# Buck-Boost_5-12V.net
KiCad netlist of a schematic drawn in Altium Designer
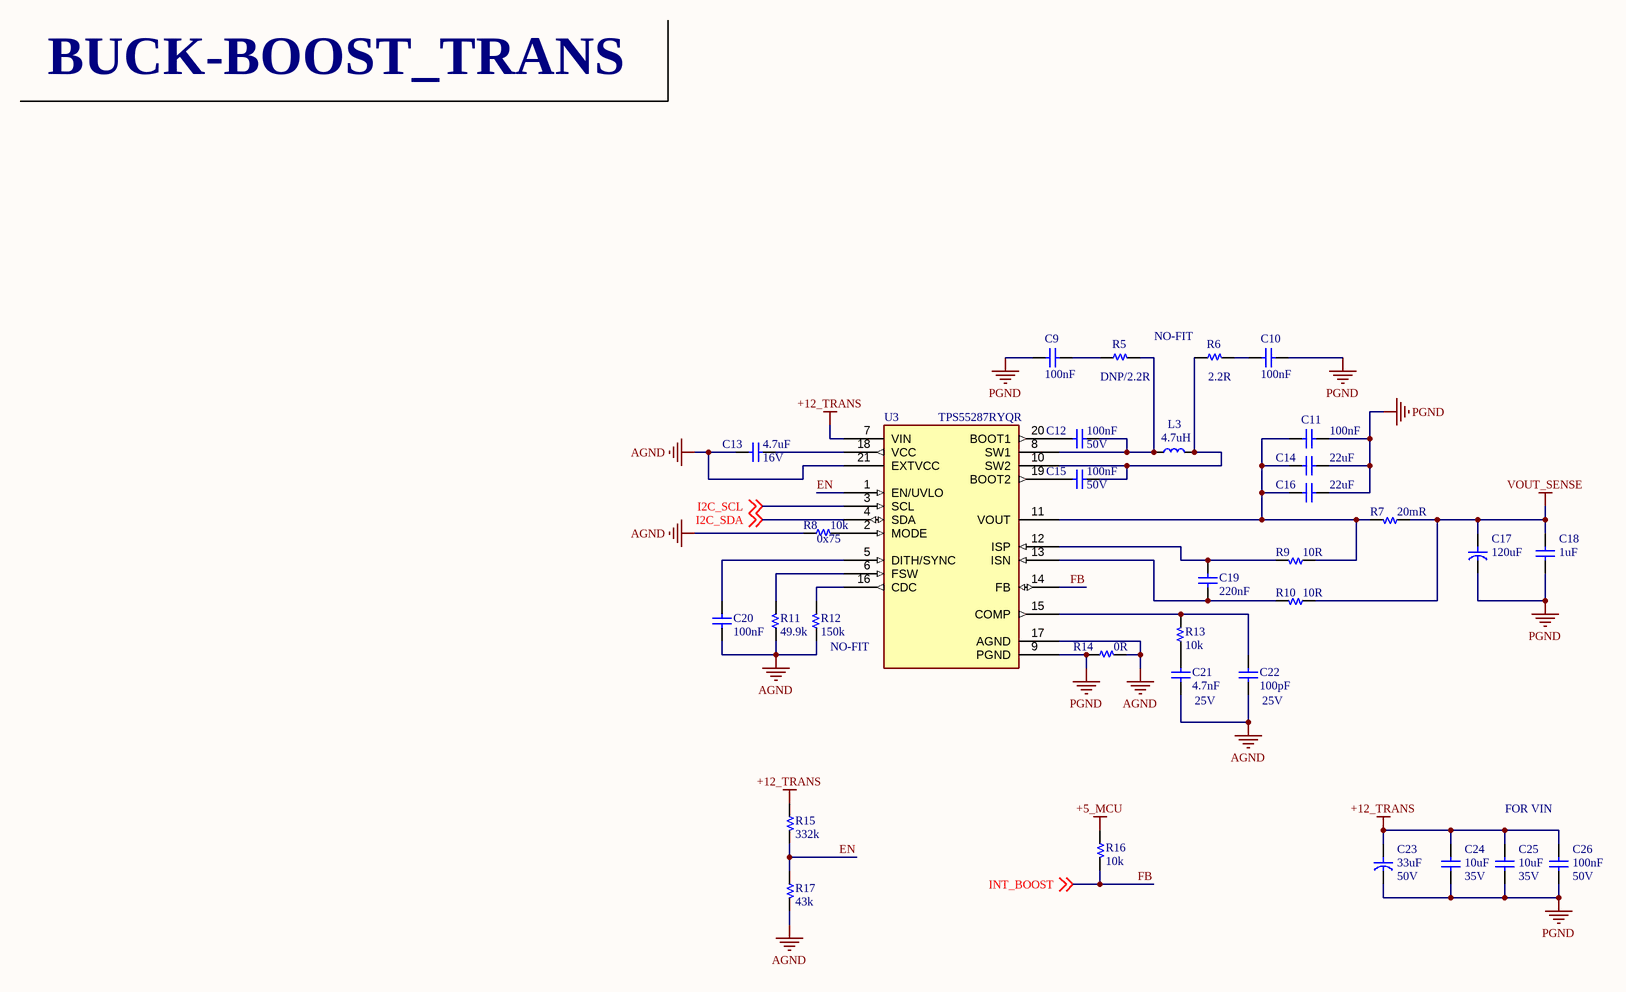
[diagram p0: Buck-Boost 5-12V.SchDoc]

(export (version "E")
  (design (tool "Eeschema 10.0.6"))
  (components
    (comp (ref "C9")
      (value "100nF")
      (footprint "C 0805")
      (description "CAP CER 0.1UF 50V X7R 0603")
      (libsource (lib "KIENASIY123_LIB") (part "Capacitor NP"))
    )
    (comp (ref "C10")
      (value "100nF")
      (footprint "C 0805")
      (description "Capacitor non-pol")
      (libsource (lib "KIENASIY123_LIB") (part "Capacitor NP"))
    )
    (comp (ref "C11")
      (value "100nF")
      (footprint "C 0402")
      (description "CAP CER 0.1UF 50V X7R 0603")
      (libsource (lib "KIENASIY123_LIB") (part "Capacitor NP"))
    )
    (comp (ref "C12")
      (value "100nF")
      (footprint "C 0603")
      (description "CAP CER 0.1UF 50V X7R 0603")
      (libsource (lib "KIENASIY123_LIB") (part "Capacitor NP"))
    )
    (comp (ref "C13")
      (value "4.7uF")
      (footprint "C 0402")
      (description "CAP CER 4.7UF 25V X6S 0603")
      (libsource (lib "KIENASIY123_LIB") (part "Capacitor NP"))
    )
    (comp (ref "C14")
      (value "22uF")
      (footprint "C 0603")
      (description "CAP CER 22UF 35V X5R 1206")
      (libsource (lib "KIENASIY123_LIB") (part "Capacitor NP"))
    )
    (comp (ref "C15")
      (value "100nF")
      (footprint "C 0603")
      (description "CAP CER 0.1UF 50V X7R 0603")
      (libsource (lib "KIENASIY123_LIB") (part "Capacitor NP"))
    )
    (comp (ref "C16")
      (value "22uF")
      (footprint "C 0603")
      (description "CAP CER 22UF 35V X5R 1206")
      (libsource (lib "KIENASIY123_LIB") (part "Capacitor NP"))
    )
    (comp (ref "C17")
      (value "120uF")
      (footprint "C SMD TAN 2917 (E)")
      (description "T543X107M025AHE060")
      (libsource (lib "KIENASIY123_LIB") (part "Capacitor"))
    )
    (comp (ref "C18")
      (value "1uF")
      (footprint "C 0603")
      (description "CAP CER 22UF 35V X5R 1206")
      (libsource (lib "KIENASIY123_LIB") (part "Capacitor NP"))
    )
    (comp (ref "C19")
      (value "220nF")
      (footprint "C 0402")
      (description "Capacitor non-pol")
      (libsource (lib "KIENASIY123_LIB") (part "Capacitor NP"))
    )
    (comp (ref "C20")
      (value "100nF")
      (footprint "C 0402")
      (description "CAP CER 0.1UF 50V X7R 0603")
      (libsource (lib "KIENASIY123_LIB") (part "Capacitor NP"))
    )
    (comp (ref "C21")
      (value "4.7nF")
      (footprint "C 0402")
      (description "Capacitor non-pol")
      (libsource (lib "KIENASIY123_LIB") (part "Capacitor NP"))
    )
    (comp (ref "C22")
      (value "100pF")
      (footprint "C 0402")
      (description "Capacitor non-pol")
      (libsource (lib "KIENASIY123_LIB") (part "Capacitor NP"))
    )
    (comp (ref "C23")
      (value "33uF")
      (footprint "C SMD TAN 2917 (E)")
      (description "T543X336M050AHE0407505")
      (libsource (lib "KIENASIY123_LIB") (part "Capacitor"))
    )
    (comp (ref "C24")
      (value "10uF")
      (footprint "C 0603")
      (description "CAP CER 10UF 35V X5R 0603")
      (libsource (lib "KIENASIY123_LIB") (part "Capacitor NP"))
    )
    (comp (ref "C25")
      (value "10uF")
      (footprint "C 0603")
      (description "CAP CER 10UF 35V X5R 0603")
      (libsource (lib "KIENASIY123_LIB") (part "Capacitor NP"))
    )
    (comp (ref "C26")
      (value "100nF")
      (footprint "C 0402")
      (description "CAP CER 0.1UF 50V X7R 0603")
      (libsource (lib "KIENASIY123_LIB") (part "Capacitor NP"))
    )
    (comp (ref "L3")
      (value "4.7uH")
      (footprint "Inductor SMD 6x5.7x4.8")
      (description "EXLA1V0505-4R7-R")
      (libsource (lib "KIENASIY123_LIB") (part "Inductor"))
    )
    (comp (ref "R5")
      (value "DNP/2.2R")
      (footprint "R 1206")
      (description "Resistor")
      (libsource (lib "KIENASIY123_LIB") (part "Resistor"))
    )
    (comp (ref "R6")
      (value "2.2R")
      (footprint "R 1206")
      (description "Resistor")
      (libsource (lib "KIENASIY123_LIB") (part "Resistor"))
    )
    (comp (ref "R7")
      (value "20mR")
      (footprint "R 1206")
      (description "Resistor")
      (libsource (lib "KIENASIY123_LIB") (part "Resistor"))
    )
    (comp (ref "R8")
      (value "10k")
      (footprint "R 0402")
      (description "RES 10K OHM 1% 1/10W 0603")
      (libsource (lib "KIENASIY123_LIB") (part "Resistor"))
    )
    (comp (ref "R9")
      (value "10R")
      (footprint "R 0402")
      (description "Resistor")
      (libsource (lib "KIENASIY123_LIB") (part "Resistor"))
    )
    (comp (ref "R10")
      (value "10R")
      (footprint "R 0402")
      (description "Resistor")
      (libsource (lib "KIENASIY123_LIB") (part "Resistor"))
    )
    (comp (ref "R11")
      (value "49.9k")
      (footprint "R 0402")
      (description "Resistor")
      (libsource (lib "KIENASIY123_LIB") (part "Resistor"))
    )
    (comp (ref "R12")
      (value "150k")
      (footprint "R 0402")
      (description "Resistor")
      (libsource (lib "KIENASIY123_LIB") (part "Resistor"))
    )
    (comp (ref "R13")
      (value "10k")
      (footprint "R 0402")
      (description "RES 10K OHM 1% 1/10W 0603")
      (libsource (lib "KIENASIY123_LIB") (part "Resistor"))
    )
    (comp (ref "R14")
      (value "0R")
      (footprint "R 2512")
      (description "Resistor")
      (libsource (lib "KIENASIY123_LIB") (part "Resistor"))
    )
    (comp (ref "R15")
      (value "332k")
      (footprint "R 0402")
      (description "RES 10K OHM 1% 1/10W 0603")
      (libsource (lib "KIENASIY123_LIB") (part "Resistor"))
    )
    (comp (ref "R16")
      (value "10k")
      (footprint "R 0402")
      (description "RES 10K OHM 1% 1/10W 0603")
      (libsource (lib "KIENASIY123_LIB") (part "Resistor"))
    )
    (comp (ref "R17")
      (value "43k")
      (footprint "R 0402")
      (description "RES 10K OHM 1% 1/10W 0603")
      (libsource (lib "KIENASIY123_LIB") (part "Resistor"))
    )
    (comp (ref "U3")
      (value "TPS55287RYQR")
      (footprint "VQFN-HR-21")
      (libsource (lib "KIENASIY123_LIB") (part "TPS55289-Q1"))
    )
  )
  (nets
    (net (code "1") (name "+5_MCU") (class "Default")
      (node (ref "R16") (pin "1") (pinfunction "1_1") (pintype "passive"))
    )
    (net (code "2") (name "+12_TRANS") (class "Default")
      (node (ref "C23") (pin "1") (pinfunction "1_1") (pintype "passive"))
      (node (ref "C24") (pin "1") (pinfunction "1_1") (pintype "passive"))
      (node (ref "C25") (pin "1") (pinfunction "1_1") (pintype "passive"))
      (node (ref "C26") (pin "1") (pinfunction "1_1") (pintype "passive"))
      (node (ref "R15") (pin "1") (pinfunction "1_1") (pintype "passive"))
      (node (ref "U3") (pin "7") (pinfunction "VIN_7") (pintype "power_in"))
    )
    (net (code "3") (name "/EN") (class "Default")
      (node (ref "R15") (pin "2") (pinfunction "2_2") (pintype "passive"))
      (node (ref "R17") (pin "1") (pinfunction "1_1") (pintype "passive"))
      (node (ref "U3") (pin "1") (pinfunction "EN/UVLO_1") (pintype "input"))
    )
    (net (code "4") (name "AGND") (class "Default")
      (node (ref "C13") (pin "2") (pinfunction "2_2") (pintype "passive"))
      (node (ref "C20") (pin "2") (pinfunction "2_2") (pintype "passive"))
      (node (ref "C21") (pin "2") (pinfunction "2_2") (pintype "passive"))
      (node (ref "C22") (pin "2") (pinfunction "2_2") (pintype "passive"))
      (node (ref "R11") (pin "1") (pinfunction "1_1") (pintype "passive"))
      (node (ref "R12") (pin "1") (pinfunction "1_1") (pintype "passive"))
      (node (ref "R14") (pin "2") (pinfunction "2_2") (pintype "passive"))
      (node (ref "R17") (pin "2") (pinfunction "2_2") (pintype "passive"))
      (node (ref "R8") (pin "1") (pinfunction "1_1") (pintype "passive"))
      (node (ref "U3") (pin "17") (pinfunction "AGND_17") (pintype "power_in"))
      (node (ref "U3") (pin "21") (pinfunction "EXTVCC_21") (pintype "power_in"))
    )
    (net (code "5") (name "I2C_SCL") (class "Default")
      (node (ref "U3") (pin "3") (pinfunction "SCL_3") (pintype "input"))
    )
    (net (code "6") (name "I2C_SDA") (class "Default")
      (node (ref "U3") (pin "4") (pinfunction "SDA_4") (pintype "bidirectional"))
    )
    (net (code "7") (name "INT_BOOST") (class "Default")
      (node (ref "R16") (pin "2") (pinfunction "2_2") (pintype "passive"))
      (node (ref "U3") (pin "14") (pinfunction "FB_14") (pintype "bidirectional"))
    )
    (net (code "8") (name "Net-(C9-Pad2)") (class "Default")
      (node (ref "C9") (pin "2") (pinfunction "2_2") (pintype "passive"))
      (node (ref "R5") (pin "1") (pinfunction "1_1") (pintype "passive"))
    )
    (net (code "9") (name "Net-(C10-Pad2)") (class "Default")
      (node (ref "C10") (pin "2") (pinfunction "2_2") (pintype "passive"))
      (node (ref "R6") (pin "1") (pinfunction "1_1") (pintype "passive"))
    )
    (net (code "10") (name "Net-(C21-Pad1)") (class "Default")
      (node (ref "C21") (pin "1") (pinfunction "1_1") (pintype "passive"))
      (node (ref "R13") (pin "1") (pinfunction "1_1") (pintype "passive"))
    )
    (net (code "11") (name "Net-(U3-BOOT1)") (class "Default")
      (node (ref "C12") (pin "1") (pinfunction "1_1") (pintype "passive"))
      (node (ref "U3") (pin "20") (pinfunction "BOOT1_20") (pintype "output"))
    )
    (net (code "12") (name "Net-(U3-BOOT2)") (class "Default")
      (node (ref "C15") (pin "1") (pinfunction "1_1") (pintype "passive"))
      (node (ref "U3") (pin "19") (pinfunction "BOOT2_19") (pintype "output"))
    )
    (net (code "13") (name "Net-(U3-CDC)") (class "Default")
      (node (ref "R12") (pin "2") (pinfunction "2_2") (pintype "passive"))
      (node (ref "U3") (pin "16") (pinfunction "CDC_16") (pintype "output"))
    )
    (net (code "14") (name "Net-(U3-COMP)") (class "Default")
      (node (ref "C22") (pin "1") (pinfunction "1_1") (pintype "passive"))
      (node (ref "R13") (pin "2") (pinfunction "2_2") (pintype "passive"))
      (node (ref "U3") (pin "15") (pinfunction "COMP_15") (pintype "output"))
    )
    (net (code "15") (name "Net-(U3-DITH{slash}SYNC)") (class "Default")
      (node (ref "C20") (pin "1") (pinfunction "1_1") (pintype "passive"))
      (node (ref "U3") (pin "5") (pinfunction "DITH/SYNC_5") (pintype "input"))
    )
    (net (code "16") (name "Net-(U3-FSW)") (class "Default")
      (node (ref "R11") (pin "2") (pinfunction "2_2") (pintype "passive"))
      (node (ref "U3") (pin "6") (pinfunction "FSW_6") (pintype "input"))
    )
    (net (code "17") (name "Net-(U3-ISN)") (class "Default")
      (node (ref "C19") (pin "1") (pinfunction "1_1") (pintype "passive"))
      (node (ref "R10") (pin "2") (pinfunction "2_2") (pintype "passive"))
      (node (ref "U3") (pin "13") (pinfunction "ISN_13") (pintype "input"))
    )
    (net (code "18") (name "Net-(U3-ISP)") (class "Default")
      (node (ref "C19") (pin "2") (pinfunction "2_2") (pintype "passive"))
      (node (ref "R9") (pin "2") (pinfunction "2_2") (pintype "passive"))
      (node (ref "U3") (pin "12") (pinfunction "ISP_12") (pintype "input"))
    )
    (net (code "19") (name "Net-(U3-MODE)") (class "Default")
      (node (ref "R8") (pin "2") (pinfunction "2_2") (pintype "passive"))
      (node (ref "U3") (pin "2") (pinfunction "MODE_2") (pintype "input"))
    )
    (net (code "20") (name "Net-(U3-SW1)") (class "Default")
      (node (ref "C12") (pin "2") (pinfunction "2_2") (pintype "passive"))
      (node (ref "L3") (pin "1") (pinfunction "1_1") (pintype "passive"))
      (node (ref "R5") (pin "2") (pinfunction "2_2") (pintype "passive"))
      (node (ref "U3") (pin "8") (pinfunction "SW1_8") (pintype "power_in"))
    )
    (net (code "21") (name "Net-(U3-SW2)") (class "Default")
      (node (ref "C15") (pin "2") (pinfunction "2_2") (pintype "passive"))
      (node (ref "L3") (pin "2") (pinfunction "2_2") (pintype "passive"))
      (node (ref "R6") (pin "2") (pinfunction "2_2") (pintype "passive"))
      (node (ref "U3") (pin "10") (pinfunction "SW2_10") (pintype "power_in"))
    )
    (net (code "22") (name "Net-(U3-VCC)") (class "Default")
      (node (ref "C13") (pin "1") (pinfunction "1_1") (pintype "passive"))
      (node (ref "U3") (pin "18") (pinfunction "VCC_18") (pintype "output"))
    )
    (net (code "23") (name "Net-(U3-VOUT)") (class "Default")
      (node (ref "C11") (pin "1") (pinfunction "1_1") (pintype "passive"))
      (node (ref "C14") (pin "1") (pinfunction "1_1") (pintype "passive"))
      (node (ref "C16") (pin "1") (pinfunction "1_1") (pintype "passive"))
      (node (ref "R7") (pin "2") (pinfunction "2_2") (pintype "passive"))
      (node (ref "R9") (pin "1") (pinfunction "1_1") (pintype "passive"))
      (node (ref "U3") (pin "11") (pinfunction "VOUT_11") (pintype "power_in"))
    )
    (net (code "24") (name "PGND") (class "Default")
      (node (ref "C10") (pin "1") (pinfunction "1_1") (pintype "passive"))
      (node (ref "C11") (pin "2") (pinfunction "2_2") (pintype "passive"))
      (node (ref "C14") (pin "2") (pinfunction "2_2") (pintype "passive"))
      (node (ref "C16") (pin "2") (pinfunction "2_2") (pintype "passive"))
      (node (ref "C17") (pin "2") (pinfunction "2_2") (pintype "passive"))
      (node (ref "C18") (pin "2") (pinfunction "2_2") (pintype "passive"))
      (node (ref "C23") (pin "2") (pinfunction "2_2") (pintype "passive"))
      (node (ref "C24") (pin "2") (pinfunction "2_2") (pintype "passive"))
      (node (ref "C25") (pin "2") (pinfunction "2_2") (pintype "passive"))
      (node (ref "C26") (pin "2") (pinfunction "2_2") (pintype "passive"))
      (node (ref "C9") (pin "1") (pinfunction "1_1") (pintype "passive"))
      (node (ref "R14") (pin "1") (pinfunction "1_1") (pintype "passive"))
      (node (ref "U3") (pin "9") (pinfunction "PGND_9") (pintype "power_in"))
    )
    (net (code "25") (name "VOUT_SENSE") (class "Default")
      (node (ref "C17") (pin "1") (pinfunction "1_1") (pintype "passive"))
      (node (ref "C18") (pin "1") (pinfunction "1_1") (pintype "passive"))
      (node (ref "R10") (pin "1") (pinfunction "1_1") (pintype "passive"))
      (node (ref "R7") (pin "1") (pinfunction "1_1") (pintype "passive"))
    )
  )
)
